# currentmeterProject2.net
KiCad netlist of a schematic drawn in EAGLE
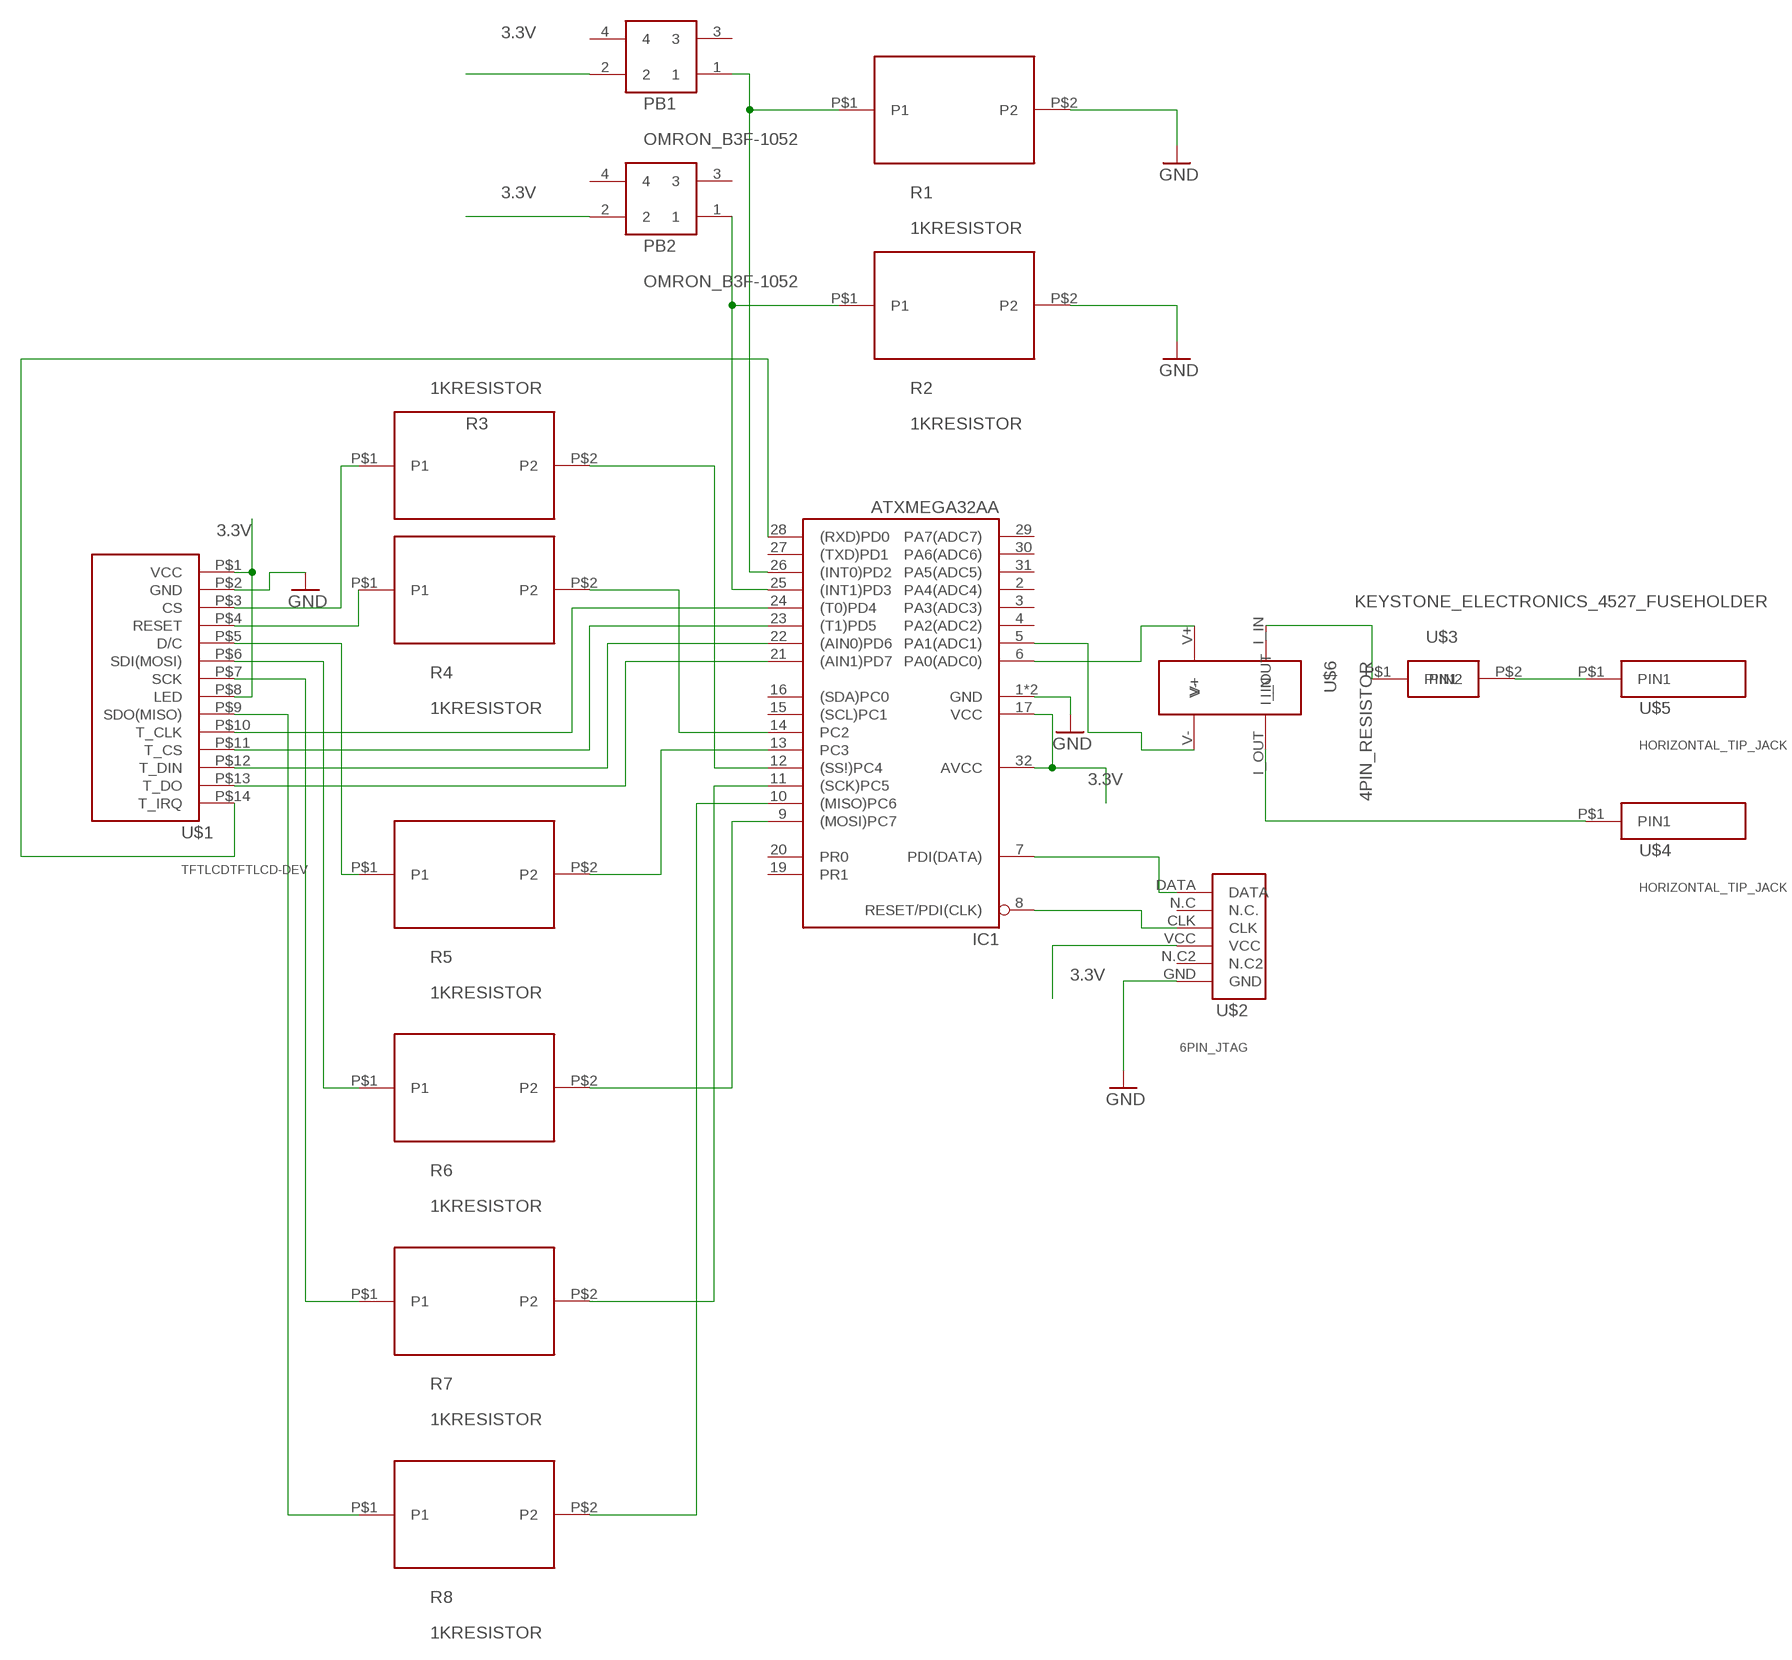
[diagram p0: schematic, sheet 1]
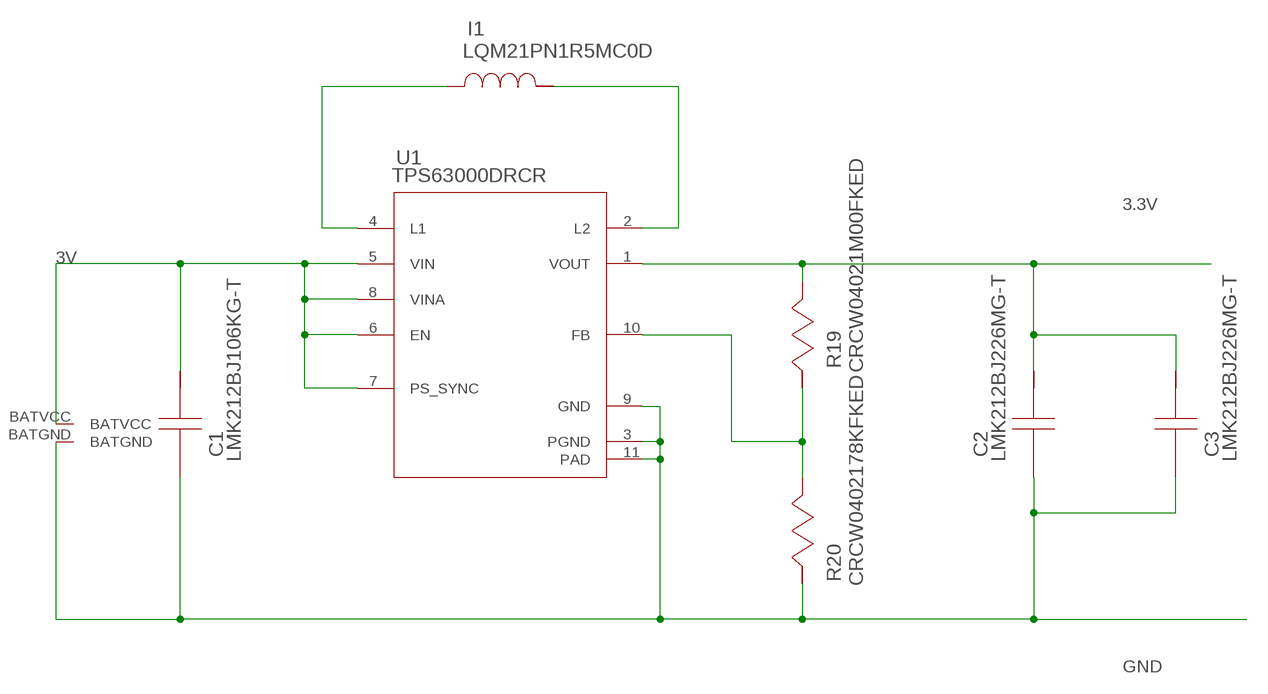
[diagram p1: schematic, sheet 2]

(export (version "E")
  (design (tool "Eeschema 10.0.6"))
  (components
    (comp (ref "C1")
      (value "LMK212BJ106KG-T")
      (footprint "eagle-import:0805")
      (libsource (lib "eagle-import") (part "LMK212BJ106KG-T"))
    )
    (comp (ref "C2")
      (value "LMK212BJ226MG-T")
      (footprint "eagle-import:0805")
      (libsource (lib "eagle-import") (part "LMK212BJ226MG-T"))
    )
    (comp (ref "C3")
      (value "LMK212BJ226MG-T")
      (footprint "eagle-import:0805")
      (libsource (lib "eagle-import") (part "LMK212BJ226MG-T"))
    )
    (comp (ref "I1")
      (value "LQM21PN1R5MC0D")
      (footprint "eagle-import:0805")
      (libsource (lib "eagle-import") (part "LQM21PN1R5MC0D"))
    )
    (comp (ref "R19")
      (value "CRCW04021M00FKED")
      (footprint "eagle-import:0402")
      (libsource (lib "eagle-import") (part "CRCW04021M00FKED"))
    )
    (comp (ref "R20")
      (value "CRCW0402178KFKED")
      (footprint "eagle-import:0402")
      (libsource (lib "eagle-import") (part "CRCW0402178KFKED"))
    )
    (comp (ref "U$12")
      (value "BATTERYHOLDER")
      (footprint "eagle-import:BATTERYHOLDER")
      (libsource (lib "eagle-import") (part "BATTERYHOLDER"))
    )
    (comp (ref "U1")
      (value "TPS63000DRCR")
      (footprint "eagle-import:DRC0010J")
      (libsource (lib "eagle-import") (part "TPS63000DRCR"))
    )
    (comp (ref "IC1")
      (value "ATXMEGA32AA")
      (footprint "eagle-import:TQFP32-08")
      (libsource (lib "eagle-import") (part "ATXMEGA32AA"))
    )
    (comp (ref "PB1")
      (value "OMRON_B3F-1052")
      (footprint "eagle-import:OMRON_B3F-1052")
      (libsource (lib "eagle-import") (part "OMRON_B3F-1052"))
    )
    (comp (ref "PB2")
      (value "OMRON_B3F-1052")
      (footprint "eagle-import:OMRON_B3F-1052")
      (libsource (lib "eagle-import") (part "OMRON_B3F-1052"))
    )
    (comp (ref "R1")
      (value "1KRESISTOR")
      (footprint "eagle-import:1KRESISTOR")
      (libsource (lib "eagle-import") (part "1KRESISTOR"))
    )
    (comp (ref "R2")
      (value "1KRESISTOR")
      (footprint "eagle-import:1KRESISTOR")
      (libsource (lib "eagle-import") (part "1KRESISTOR"))
    )
    (comp (ref "R3")
      (value "1KRESISTOR")
      (footprint "eagle-import:1KRESISTOR")
      (libsource (lib "eagle-import") (part "1KRESISTOR"))
    )
    (comp (ref "R4")
      (value "1KRESISTOR")
      (footprint "eagle-import:1KRESISTOR")
      (libsource (lib "eagle-import") (part "1KRESISTOR"))
    )
    (comp (ref "R5")
      (value "1KRESISTOR")
      (footprint "eagle-import:1KRESISTOR")
      (libsource (lib "eagle-import") (part "1KRESISTOR"))
    )
    (comp (ref "R6")
      (value "1KRESISTOR")
      (footprint "eagle-import:1KRESISTOR")
      (libsource (lib "eagle-import") (part "1KRESISTOR"))
    )
    (comp (ref "R7")
      (value "1KRESISTOR")
      (footprint "eagle-import:1KRESISTOR")
      (libsource (lib "eagle-import") (part "1KRESISTOR"))
    )
    (comp (ref "R8")
      (value "1KRESISTOR")
      (footprint "eagle-import:1KRESISTOR")
      (libsource (lib "eagle-import") (part "1KRESISTOR"))
    )
    (comp (ref "U$1")
      (value "TFTLCDTFTLCD-DEV")
      (footprint "eagle-import:TFTLCDTFTLCD-DEV")
      (libsource (lib "eagle-import") (part "TFTLCDTFTLCD-DEV"))
    )
    (comp (ref "U$2")
      (value "6PIN_JTAG")
      (footprint "eagle-import:6PIN_JTAG")
      (libsource (lib "eagle-import") (part "6PIN_JTAG"))
    )
    (comp (ref "U$3")
      (value "KEYSTONE_ELECTRONICS_4527_FUSEHOLDER")
      (footprint "eagle-import:KEYSTONE_ELECTRONICS_4527_FUSEHOLDER")
      (libsource (lib "eagle-import") (part "KEYSTONE_ELECTRONICS_4527_FUSEHOLDER"))
    )
    (comp (ref "U$4")
      (value "HORIZONTAL_TIP_JACK")
      (footprint "eagle-import:HORIZONTAL_TIP_JACK")
      (libsource (lib "eagle-import") (part "HORIZONTAL_TIP_JACK"))
    )
    (comp (ref "U$5")
      (value "HORIZONTAL_TIP_JACK")
      (footprint "eagle-import:HORIZONTAL_TIP_JACK")
      (libsource (lib "eagle-import") (part "HORIZONTAL_TIP_JACK"))
    )
    (comp (ref "U$6")
      (value "4PIN_RESISTOR")
      (footprint "eagle-import:4PIN_RESISTOR")
      (libsource (lib "eagle-import") (part "4PIN_RESISTOR"))
    )
  )
  (nets
    (net (code "1") (name "3.3V") (class "Default")
      (node (ref "C2") (pin "1") (pinfunction "1_1") (pintype "passive"))
      (node (ref "C3") (pin "1") (pinfunction "1_1") (pintype "passive"))
      (node (ref "IC1") (pin "17") (pinfunction "VCC_17") (pintype "power_in"))
      (node (ref "IC1") (pin "32") (pinfunction "AVCC_32") (pintype "power_in"))
      (node (ref "PB1") (pin "2") (pinfunction "2_2") (pintype "passive"))
      (node (ref "PB2") (pin "2") (pinfunction "2_2") (pintype "passive"))
      (node (ref "R19") (pin "1") (pinfunction "1_1") (pintype "passive"))
      (node (ref "U$1") (pin "P$1") (pinfunction "VCC_P$1") (pintype "passive"))
      (node (ref "U$1") (pin "P$8") (pinfunction "LED_P$8") (pintype "passive"))
      (node (ref "U$2") (pin "VCC") (pinfunction "VCC_VCC") (pintype "power_in"))
      (node (ref "U1") (pin "1") (pinfunction "VOUT_1") (pintype "power_in"))
    )
    (net (code "2") (name "3V") (class "Default")
      (node (ref "C1") (pin "1") (pinfunction "1_1") (pintype "passive"))
      (node (ref "U$12") (pin "BATVCC") (pinfunction "BATVCC_BATVCC") (pintype "power_in"))
      (node (ref "U1") (pin "5") (pinfunction "VIN_5") (pintype "power_in"))
      (node (ref "U1") (pin "6") (pinfunction "EN_6") (pintype "input"))
      (node (ref "U1") (pin "7") (pinfunction "PS_SYNC_7") (pintype "input"))
      (node (ref "U1") (pin "8") (pinfunction "VINA_8") (pintype "power_in"))
    )
    (net (code "3") (name "GND") (class "Default")
      (node (ref "C1") (pin "2") (pinfunction "2_2") (pintype "passive"))
      (node (ref "C2") (pin "2") (pinfunction "2_2") (pintype "passive"))
      (node (ref "C3") (pin "2") (pinfunction "2_2") (pintype "passive"))
      (node (ref "IC1") (pin "1") (pinfunction "GND_1") (pintype "power_in"))
      (node (ref "IC1") (pin "18") (pinfunction "GND_18") (pintype "power_in"))
      (node (ref "R1") (pin "P$2") (pinfunction "P2_P$2") (pintype "passive"))
      (node (ref "R2") (pin "P$2") (pinfunction "P2_P$2") (pintype "passive"))
      (node (ref "R20") (pin "2") (pinfunction "2_2") (pintype "passive"))
      (node (ref "U$1") (pin "P$2") (pinfunction "GND_P$2") (pintype "passive"))
      (node (ref "U$12") (pin "BATGND") (pinfunction "BATGND_BATGND") (pintype "power_in"))
      (node (ref "U$2") (pin "GND") (pinfunction "GND_GND") (pintype "power_in"))
      (node (ref "U1") (pin "11") (pinfunction "PAD_11") (pintype "power_in"))
      (node (ref "U1") (pin "3") (pinfunction "PGND_3") (pintype "power_in"))
      (node (ref "U1") (pin "9") (pinfunction "GND_9") (pintype "power_in"))
    )
    (net (code "4") (name "Net-(IC1-(AIN0)PD6)") (class "Default")
      (node (ref "IC1") (pin "22") (pinfunction "(AIN0)PD6_22") (pintype "bidirectional"))
      (node (ref "U$1") (pin "P$12") (pinfunction "T_DIN_P$12") (pintype "passive"))
    )
    (net (code "5") (name "Net-(IC1-(AIN1)PD7)") (class "Default")
      (node (ref "IC1") (pin "21") (pinfunction "(AIN1)PD7_21") (pintype "bidirectional"))
      (node (ref "U$1") (pin "P$13") (pinfunction "T_DO_P$13") (pintype "passive"))
    )
    (net (code "6") (name "Net-(IC1-(INT0)PD2)") (class "Default")
      (node (ref "IC1") (pin "26") (pinfunction "(INT0)PD2_26") (pintype "bidirectional"))
      (node (ref "PB1") (pin "1") (pinfunction "1_1") (pintype "passive"))
      (node (ref "R1") (pin "P$1") (pinfunction "P1_P$1") (pintype "passive"))
    )
    (net (code "7") (name "Net-(IC1-(INT1)PD3)") (class "Default")
      (node (ref "IC1") (pin "25") (pinfunction "(INT1)PD3_25") (pintype "bidirectional"))
      (node (ref "PB2") (pin "1") (pinfunction "1_1") (pintype "passive"))
      (node (ref "R2") (pin "P$1") (pinfunction "P1_P$1") (pintype "passive"))
    )
    (net (code "8") (name "Net-(IC1-(MISO)PC6)") (class "Default")
      (node (ref "IC1") (pin "10") (pinfunction "(MISO)PC6_10") (pintype "bidirectional"))
      (node (ref "R8") (pin "P$2") (pinfunction "P2_P$2") (pintype "passive"))
    )
    (net (code "9") (name "Net-(IC1-(MOSI)PC7)") (class "Default")
      (node (ref "IC1") (pin "9") (pinfunction "(MOSI)PC7_9") (pintype "bidirectional"))
      (node (ref "R6") (pin "P$2") (pinfunction "P2_P$2") (pintype "passive"))
    )
    (net (code "10") (name "Net-(IC1-(RXD)PD0)") (class "Default")
      (node (ref "IC1") (pin "28") (pinfunction "(RXD)PD0_28") (pintype "bidirectional"))
      (node (ref "U$1") (pin "P$14") (pinfunction "T_IRQ_P$14") (pintype "passive"))
    )
    (net (code "11") (name "Net-(IC1-(SCK)PC5)") (class "Default")
      (node (ref "IC1") (pin "11") (pinfunction "(SCK)PC5_11") (pintype "bidirectional"))
      (node (ref "R7") (pin "P$2") (pinfunction "P2_P$2") (pintype "passive"))
    )
    (net (code "12") (name "Net-(IC1-(SS~{})PC4)") (class "Default")
      (node (ref "IC1") (pin "12") (pinfunction "(SS~{})PC4_12") (pintype "bidirectional"))
      (node (ref "R3") (pin "P$2") (pinfunction "P2_P$2") (pintype "passive"))
    )
    (net (code "13") (name "Net-(IC1-(T0)PD4)") (class "Default")
      (node (ref "IC1") (pin "24") (pinfunction "(T0)PD4_24") (pintype "bidirectional"))
      (node (ref "U$1") (pin "P$10") (pinfunction "T_CLK_P$10") (pintype "passive"))
    )
    (net (code "14") (name "Net-(IC1-(T1)PD5)") (class "Default")
      (node (ref "IC1") (pin "23") (pinfunction "(T1)PD5_23") (pintype "bidirectional"))
      (node (ref "U$1") (pin "P$11") (pinfunction "T_CS_P$11") (pintype "passive"))
    )
    (net (code "15") (name "Net-(IC1-PA0(ADC0))") (class "Default")
      (node (ref "IC1") (pin "6") (pinfunction "PA0(ADC0)_6") (pintype "bidirectional"))
      (node (ref "U$6") (pin "V+") (pinfunction "V+_V+") (pintype "passive"))
    )
    (net (code "16") (name "Net-(IC1-PA1(ADC1))") (class "Default")
      (node (ref "IC1") (pin "5") (pinfunction "PA1(ADC1)_5") (pintype "bidirectional"))
      (node (ref "U$6") (pin "V-") (pinfunction "V-_V-") (pintype "passive"))
    )
    (net (code "17") (name "Net-(IC1-PC2)") (class "Default")
      (node (ref "IC1") (pin "14") (pinfunction "PC2_14") (pintype "bidirectional"))
      (node (ref "R4") (pin "P$2") (pinfunction "P2_P$2") (pintype "passive"))
    )
    (net (code "18") (name "Net-(IC1-PC3)") (class "Default")
      (node (ref "IC1") (pin "13") (pinfunction "PC3_13") (pintype "bidirectional"))
      (node (ref "R5") (pin "P$2") (pinfunction "P2_P$2") (pintype "passive"))
    )
    (net (code "19") (name "Net-(IC1-PDI(DATA))") (class "Default")
      (node (ref "IC1") (pin "7") (pinfunction "PDI(DATA)_7") (pintype "bidirectional"))
      (node (ref "U$2") (pin "DATA") (pinfunction "DATA_DATA") (pintype "bidirectional"))
    )
    (net (code "20") (name "Net-(IC1-RESET{slash}PDI(CLK))") (class "Default")
      (node (ref "IC1") (pin "8") (pinfunction "RESET/PDI(CLK)_8") (pintype "input"))
      (node (ref "U$2") (pin "CLK") (pinfunction "CLK_CLK") (pintype "bidirectional"))
    )
    (net (code "21") (name "Net-(R3-P1)") (class "Default")
      (node (ref "R3") (pin "P$1") (pinfunction "P1_P$1") (pintype "passive"))
      (node (ref "U$1") (pin "P$3") (pinfunction "CS_P$3") (pintype "passive"))
    )
    (net (code "22") (name "Net-(R4-P1)") (class "Default")
      (node (ref "R4") (pin "P$1") (pinfunction "P1_P$1") (pintype "passive"))
      (node (ref "U$1") (pin "P$4") (pinfunction "RESET_P$4") (pintype "passive"))
    )
    (net (code "23") (name "Net-(R5-P1)") (class "Default")
      (node (ref "R5") (pin "P$1") (pinfunction "P1_P$1") (pintype "passive"))
      (node (ref "U$1") (pin "P$5") (pinfunction "D/C_P$5") (pintype "passive"))
    )
    (net (code "24") (name "Net-(R6-P1)") (class "Default")
      (node (ref "R6") (pin "P$1") (pinfunction "P1_P$1") (pintype "passive"))
      (node (ref "U$1") (pin "P$6") (pinfunction "SDI(MOSI)_P$6") (pintype "passive"))
    )
    (net (code "25") (name "Net-(R7-P1)") (class "Default")
      (node (ref "R7") (pin "P$1") (pinfunction "P1_P$1") (pintype "passive"))
      (node (ref "U$1") (pin "P$7") (pinfunction "SCK_P$7") (pintype "passive"))
    )
    (net (code "26") (name "Net-(R8-P1)") (class "Default")
      (node (ref "R8") (pin "P$1") (pinfunction "P1_P$1") (pintype "passive"))
      (node (ref "U$1") (pin "P$9") (pinfunction "SDO(MISO)_P$9") (pintype "passive"))
    )
    (net (code "27") (name "Net-(U$3-PIN1)") (class "Default")
      (node (ref "U$3") (pin "P$1") (pinfunction "PIN1_P$1") (pintype "passive"))
      (node (ref "U$6") (pin "I_IN") (pinfunction "I_IN_I_IN") (pintype "passive"))
    )
    (net (code "28") (name "Net-(U$3-PIN2)") (class "Default")
      (node (ref "U$3") (pin "P$2") (pinfunction "PIN2_P$2") (pintype "passive"))
      (node (ref "U$5") (pin "P$1") (pinfunction "PIN1_P$1") (pintype "passive"))
    )
    (net (code "29") (name "Net-(U$4-PIN1)") (class "Default")
      (node (ref "U$4") (pin "P$1") (pinfunction "PIN1_P$1") (pintype "passive"))
      (node (ref "U$6") (pin "I_OUT") (pinfunction "I_OUT_I_OUT") (pintype "passive"))
    )
    (net (code "30") (name "Net-(U1-FB)") (class "Default")
      (node (ref "R19") (pin "2") (pinfunction "2_2") (pintype "passive"))
      (node (ref "R20") (pin "1") (pinfunction "1_1") (pintype "passive"))
      (node (ref "U1") (pin "10") (pinfunction "FB_10") (pintype "input"))
    )
    (net (code "31") (name "Net-(U1-L1)") (class "Default")
      (node (ref "I1") (pin "1") (pinfunction "1_1") (pintype "passive"))
      (node (ref "U1") (pin "4") (pinfunction "L1_4") (pintype "passive"))
    )
    (net (code "32") (name "Net-(U1-L2)") (class "Default")
      (node (ref "I1") (pin "2") (pinfunction "2_2") (pintype "passive"))
      (node (ref "U1") (pin "2") (pinfunction "L2_2") (pintype "passive"))
    )
    (net (code "33") (name "unconnected-(IC1-(SCL)PC1-Pad15)") (class "Default")
      (node (ref "IC1") (pin "15") (pinfunction "(SCL)PC1_15") (pintype "bidirectional"))
    )
    (net (code "34") (name "unconnected-(IC1-(SDA)PC0-Pad16)") (class "Default")
      (node (ref "IC1") (pin "16") (pinfunction "(SDA)PC0_16") (pintype "bidirectional"))
    )
    (net (code "35") (name "unconnected-(IC1-(TXD)PD1-Pad27)") (class "Default")
      (node (ref "IC1") (pin "27") (pinfunction "(TXD)PD1_27") (pintype "bidirectional"))
    )
    (net (code "36") (name "unconnected-(IC1-PA2(ADC2)-Pad4)") (class "Default")
      (node (ref "IC1") (pin "4") (pinfunction "PA2(ADC2)_4") (pintype "bidirectional"))
    )
    (net (code "37") (name "unconnected-(IC1-PA3(ADC3)-Pad3)") (class "Default")
      (node (ref "IC1") (pin "3") (pinfunction "PA3(ADC3)_3") (pintype "bidirectional"))
    )
    (net (code "38") (name "unconnected-(IC1-PA4(ADC4)-Pad2)") (class "Default")
      (node (ref "IC1") (pin "2") (pinfunction "PA4(ADC4)_2") (pintype "bidirectional"))
    )
    (net (code "39") (name "unconnected-(IC1-PA5(ADC5)-Pad31)") (class "Default")
      (node (ref "IC1") (pin "31") (pinfunction "PA5(ADC5)_31") (pintype "bidirectional"))
    )
    (net (code "40") (name "unconnected-(IC1-PA6(ADC6)-Pad30)") (class "Default")
      (node (ref "IC1") (pin "30") (pinfunction "PA6(ADC6)_30") (pintype "bidirectional"))
    )
    (net (code "41") (name "unconnected-(IC1-PA7(ADC7)-Pad29)") (class "Default")
      (node (ref "IC1") (pin "29") (pinfunction "PA7(ADC7)_29") (pintype "bidirectional"))
    )
    (net (code "42") (name "unconnected-(IC1-PR0-Pad20)") (class "Default")
      (node (ref "IC1") (pin "20") (pinfunction "PR0_20") (pintype "bidirectional"))
    )
    (net (code "43") (name "unconnected-(IC1-PR1-Pad19)") (class "Default")
      (node (ref "IC1") (pin "19") (pinfunction "PR1_19") (pintype "bidirectional"))
    )
    (net (code "44") (name "unconnected-(PB1-Pad3)") (class "Default")
      (node (ref "PB1") (pin "3") (pinfunction "3_3") (pintype "passive"))
    )
    (net (code "45") (name "unconnected-(PB1-Pad4)") (class "Default")
      (node (ref "PB1") (pin "4") (pinfunction "4_4") (pintype "passive"))
    )
    (net (code "46") (name "unconnected-(PB2-Pad3)") (class "Default")
      (node (ref "PB2") (pin "3") (pinfunction "3_3") (pintype "passive"))
    )
    (net (code "47") (name "unconnected-(PB2-Pad4)") (class "Default")
      (node (ref "PB2") (pin "4") (pinfunction "4_4") (pintype "passive"))
    )
    (net (code "48") (name "unconnected-(U$2-N.C.-PadN.C)") (class "Default")
      (node (ref "U$2") (pin "N.C") (pinfunction "N.C._N.C") (pintype "no_connect"))
    )
    (net (code "49") (name "unconnected-(U$2-PadN.C2)") (class "Default")
      (node (ref "U$2") (pin "N.C2") (pinfunction "N.C2_N.C2") (pintype "no_connect"))
    )
  )
)
